# ftExtender.net
KiCad netlist of a schematic drawn in EAGLE
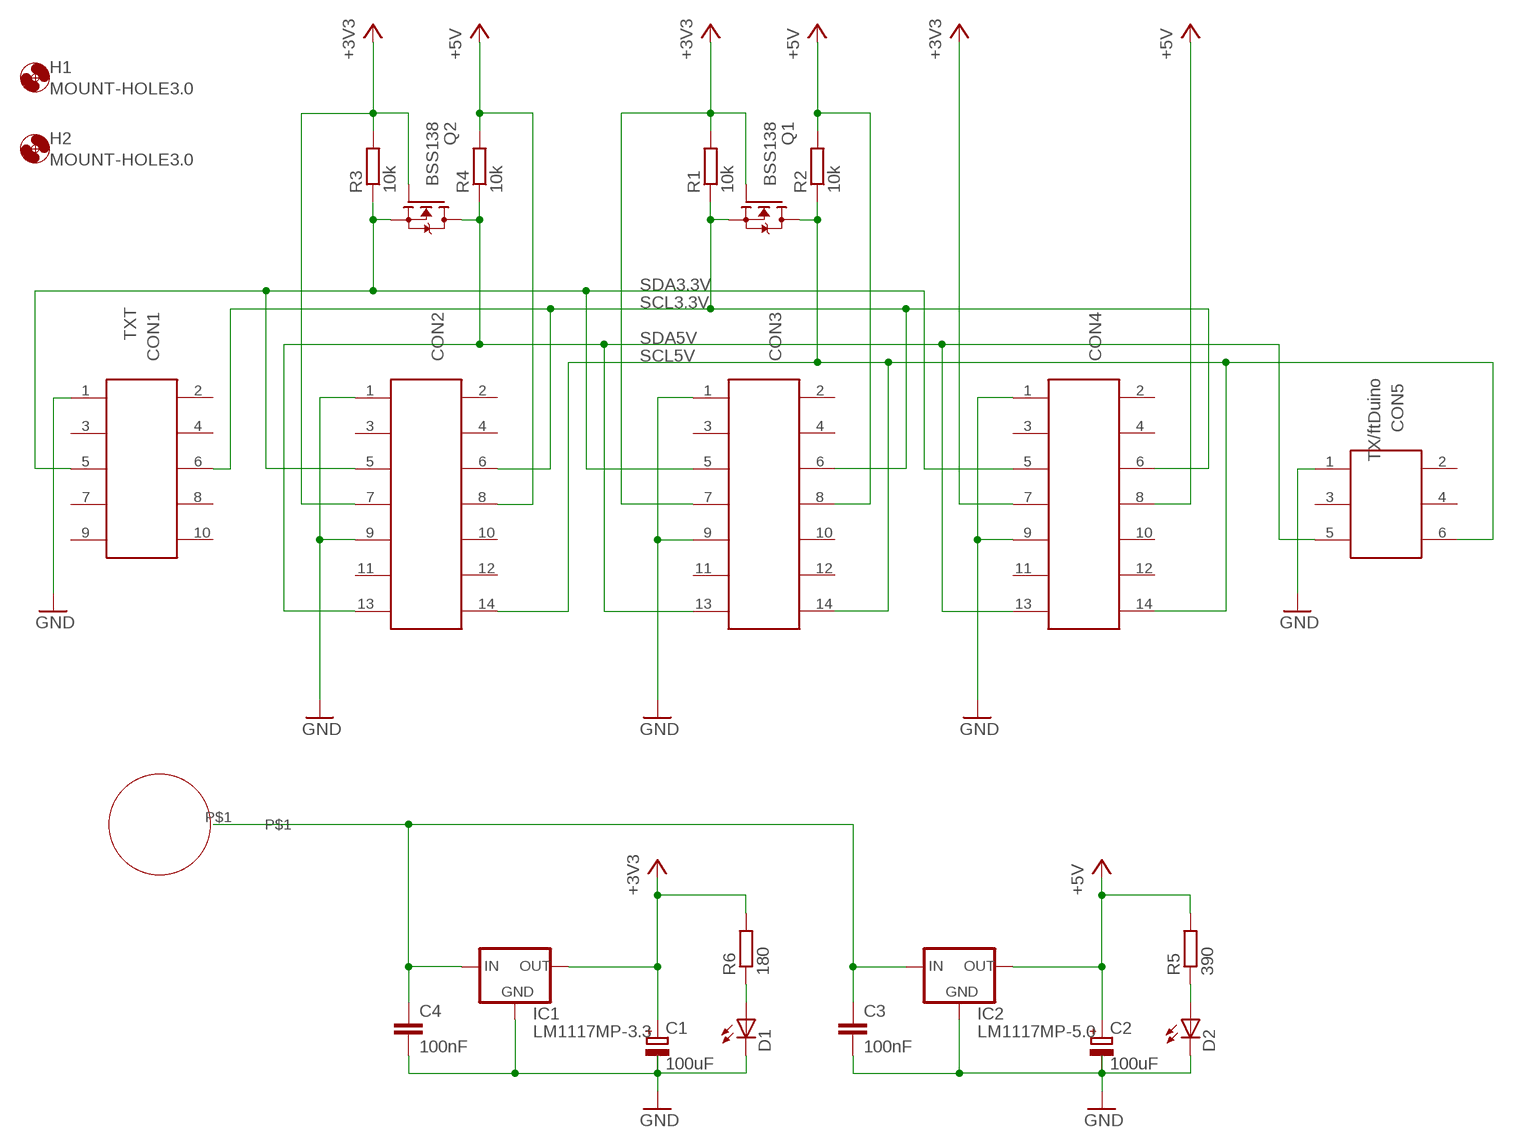
[diagram p0: schematic, sheet 1]

(export (version "E")
  (design (tool "Eeschema 10.0.6"))
  (components
    (comp (ref "+9V")
      (value "BUNDHUELSE")
      (footprint "eagle-import:BUNDHUELSE")
      (libsource (lib "eagle-import") (part "BUNDHUELSE"))
    )
    (comp (ref "C1")
      (value "100uF")
      (footprint "eagle-import:CT3528")
      (libsource (lib "eagle-import") (part "CPOL-EUCT3528"))
    )
    (comp (ref "C2")
      (value "100uF")
      (footprint "eagle-import:CT3528")
      (libsource (lib "eagle-import") (part "CPOL-EUCT3528"))
    )
    (comp (ref "C3")
      (value "100nF")
      (footprint "eagle-import:C0603K")
      (libsource (lib "eagle-import") (part "C-EUC0603K"))
    )
    (comp (ref "C4")
      (value "100nF")
      (footprint "eagle-import:C0603K")
      (libsource (lib "eagle-import") (part "C-EUC0603K"))
    )
    (comp (ref "CON1")
      (value "TXT")
      (footprint "eagle-import:612X1020621")
      (libsource (lib "eagle-import") (part "612X1020621"))
    )
    (comp (ref "CON2")
      (value "612X1420621")
      (footprint "eagle-import:612X1420621")
      (libsource (lib "eagle-import") (part "612X1420621"))
    )
    (comp (ref "CON3")
      (value "612X1420621")
      (footprint "eagle-import:612X1420621")
      (libsource (lib "eagle-import") (part "612X1420621"))
    )
    (comp (ref "CON4")
      (value "612X1420621")
      (footprint "eagle-import:612X1420621")
      (libsource (lib "eagle-import") (part "612X1420621"))
    )
    (comp (ref "CON5")
      (value "TX/ftDuino")
      (footprint "eagle-import:SMTHEADER06")
      (libsource (lib "eagle-import") (part "SMTHEADER06"))
    )
    (comp (ref "D1")
      (value "LEDCHIP-LED0805")
      (footprint "eagle-import:CHIP-LED0805")
      (libsource (lib "eagle-import") (part "LEDCHIP-LED0805"))
    )
    (comp (ref "D2")
      (value "LEDCHIP-LED0805")
      (footprint "eagle-import:CHIP-LED0805")
      (libsource (lib "eagle-import") (part "LEDCHIP-LED0805"))
    )
    (comp (ref "H1")
      (value "MOUNT-HOLE3.0")
      (footprint "eagle-import:3,0")
      (libsource (lib "eagle-import") (part "MOUNT-HOLE3.0"))
    )
    (comp (ref "H2")
      (value "MOUNT-HOLE3.0")
      (footprint "eagle-import:3,0")
      (libsource (lib "eagle-import") (part "MOUNT-HOLE3.0"))
    )
    (comp (ref "IC1")
      (value "LM1117MP-3.3")
      (footprint "eagle-import:SOT223")
      (fields (field (name "MF") "Texas Instruments"))
      (libsource (lib "eagle-import") (part "LM1117?-MP3.3"))
    )
    (comp (ref "IC2")
      (value "LM1117MP-5.0")
      (footprint "eagle-import:SOT223")
      (fields (field (name "MF") "Texas Instruments"))
      (libsource (lib "eagle-import") (part "LM1117?-MP5.0"))
    )
    (comp (ref "Q1")
      (value "BSS138")
      (footprint "eagle-import:SOT23")
      (fields (field (name "MF") "Fairchild"))
      (libsource (lib "eagle-import") (part "BSS138"))
    )
    (comp (ref "Q2")
      (value "BSS138")
      (footprint "eagle-import:SOT23")
      (fields (field (name "MF") "Fairchild"))
      (libsource (lib "eagle-import") (part "BSS138"))
    )
    (comp (ref "R1")
      (value "10k")
      (footprint "eagle-import:R0603")
      (libsource (lib "eagle-import") (part "R-EU_R0603"))
    )
    (comp (ref "R2")
      (value "10k")
      (footprint "eagle-import:R0603")
      (libsource (lib "eagle-import") (part "R-EU_R0603"))
    )
    (comp (ref "R3")
      (value "10k")
      (footprint "eagle-import:R0603")
      (libsource (lib "eagle-import") (part "R-EU_R0603"))
    )
    (comp (ref "R4")
      (value "10k")
      (footprint "eagle-import:R0603")
      (libsource (lib "eagle-import") (part "R-EU_R0603"))
    )
    (comp (ref "R5")
      (value "390")
      (footprint "eagle-import:R0603")
      (libsource (lib "eagle-import") (part "R-EU_R0603"))
    )
    (comp (ref "R6")
      (value "180")
      (footprint "eagle-import:R0603")
      (libsource (lib "eagle-import") (part "R-EU_R0603"))
    )
  )
  (nets
    (net (code "1") (name "+3V3") (class "Default")
      (node (ref "C1") (pin "-") (pinfunction "+_-") (pintype "passive"))
      (node (ref "CON2") (pin "7") (pinfunction "7_7") (pintype "passive"))
      (node (ref "CON3") (pin "7") (pinfunction "7_7") (pintype "passive"))
      (node (ref "CON4") (pin "7") (pinfunction "7_7") (pintype "passive"))
      (node (ref "IC1") (pin "2") (pinfunction "OUT_2") (pintype "passive"))
      (node (ref "IC1") (pin "4") (pinfunction "OUT_4") (pintype "passive"))
      (node (ref "Q1") (pin "1") (pinfunction "G_1") (pintype "passive"))
      (node (ref "Q2") (pin "1") (pinfunction "G_1") (pintype "passive"))
      (node (ref "R1") (pin "2") (pinfunction "2_2") (pintype "passive"))
      (node (ref "R3") (pin "2") (pinfunction "2_2") (pintype "passive"))
      (node (ref "R6") (pin "2") (pinfunction "2_2") (pintype "passive"))
    )
    (net (code "2") (name "+5V") (class "Default")
      (node (ref "C2") (pin "-") (pinfunction "+_-") (pintype "passive"))
      (node (ref "CON2") (pin "8") (pinfunction "8_8") (pintype "passive"))
      (node (ref "CON3") (pin "8") (pinfunction "8_8") (pintype "passive"))
      (node (ref "CON4") (pin "8") (pinfunction "8_8") (pintype "passive"))
      (node (ref "IC2") (pin "2") (pinfunction "OUT_2") (pintype "passive"))
      (node (ref "IC2") (pin "4") (pinfunction "OUT_4") (pintype "passive"))
      (node (ref "R2") (pin "2") (pinfunction "2_2") (pintype "passive"))
      (node (ref "R4") (pin "2") (pinfunction "2_2") (pintype "passive"))
      (node (ref "R5") (pin "2") (pinfunction "2_2") (pintype "passive"))
    )
    (net (code "3") (name "/SCL3.3V") (class "Default")
      (node (ref "CON1") (pin "6") (pinfunction "6_6") (pintype "passive"))
      (node (ref "CON2") (pin "6") (pinfunction "6_6") (pintype "passive"))
      (node (ref "CON3") (pin "6") (pinfunction "6_6") (pintype "passive"))
      (node (ref "CON4") (pin "6") (pinfunction "6_6") (pintype "passive"))
      (node (ref "Q1") (pin "2") (pinfunction "S_2") (pintype "passive"))
      (node (ref "R1") (pin "1") (pinfunction "1_1") (pintype "passive"))
    )
    (net (code "4") (name "/SCL5V") (class "Default")
      (node (ref "CON2") (pin "14") (pinfunction "14_14") (pintype "passive"))
      (node (ref "CON3") (pin "14") (pinfunction "14_14") (pintype "passive"))
      (node (ref "CON4") (pin "14") (pinfunction "14_14") (pintype "passive"))
      (node (ref "CON5") (pin "6") (pinfunction "6_6") (pintype "passive"))
      (node (ref "Q1") (pin "3") (pinfunction "D_3") (pintype "passive"))
      (node (ref "R2") (pin "1") (pinfunction "1_1") (pintype "passive"))
    )
    (net (code "5") (name "/SDA3.3V") (class "Default")
      (node (ref "CON1") (pin "5") (pinfunction "5_5") (pintype "passive"))
      (node (ref "CON2") (pin "5") (pinfunction "5_5") (pintype "passive"))
      (node (ref "CON3") (pin "5") (pinfunction "5_5") (pintype "passive"))
      (node (ref "CON4") (pin "5") (pinfunction "5_5") (pintype "passive"))
      (node (ref "Q2") (pin "2") (pinfunction "S_2") (pintype "passive"))
      (node (ref "R3") (pin "1") (pinfunction "1_1") (pintype "passive"))
    )
    (net (code "6") (name "/SDA5V") (class "Default")
      (node (ref "CON2") (pin "13") (pinfunction "13_13") (pintype "passive"))
      (node (ref "CON3") (pin "13") (pinfunction "13_13") (pintype "passive"))
      (node (ref "CON4") (pin "13") (pinfunction "13_13") (pintype "passive"))
      (node (ref "CON5") (pin "5") (pinfunction "5_5") (pintype "passive"))
      (node (ref "Q2") (pin "3") (pinfunction "D_3") (pintype "passive"))
      (node (ref "R4") (pin "1") (pinfunction "1_1") (pintype "passive"))
    )
    (net (code "7") (name "GND") (class "Default")
      (node (ref "C1") (pin "+") (pinfunction "-_+") (pintype "passive"))
      (node (ref "C2") (pin "+") (pinfunction "-_+") (pintype "passive"))
      (node (ref "C3") (pin "2") (pinfunction "2_2") (pintype "passive"))
      (node (ref "C4") (pin "2") (pinfunction "2_2") (pintype "passive"))
      (node (ref "CON1") (pin "1") (pinfunction "1_1") (pintype "passive"))
      (node (ref "CON2") (pin "1") (pinfunction "1_1") (pintype "passive"))
      (node (ref "CON2") (pin "9") (pinfunction "9_9") (pintype "passive"))
      (node (ref "CON3") (pin "1") (pinfunction "1_1") (pintype "passive"))
      (node (ref "CON3") (pin "9") (pinfunction "9_9") (pintype "passive"))
      (node (ref "CON4") (pin "1") (pinfunction "1_1") (pintype "passive"))
      (node (ref "CON4") (pin "9") (pinfunction "9_9") (pintype "passive"))
      (node (ref "CON5") (pin "1") (pinfunction "1_1") (pintype "passive"))
      (node (ref "D1") (pin "C") (pinfunction "C_C") (pintype "passive"))
      (node (ref "D2") (pin "C") (pinfunction "C_C") (pintype "passive"))
      (node (ref "IC1") (pin "1") (pinfunction "GND_1") (pintype "input"))
      (node (ref "IC2") (pin "1") (pinfunction "GND_1") (pintype "input"))
    )
    (net (code "8") (name "Net-(D1-PadA)") (class "Default")
      (node (ref "D1") (pin "A") (pinfunction "A_A") (pintype "passive"))
      (node (ref "R6") (pin "1") (pinfunction "1_1") (pintype "passive"))
    )
    (net (code "9") (name "Net-(D2-PadA)") (class "Default")
      (node (ref "D2") (pin "A") (pinfunction "A_A") (pintype "passive"))
      (node (ref "R5") (pin "1") (pinfunction "1_1") (pintype "passive"))
    )
    (net (code "10") (name "Net-(IC1-IN)") (class "Default")
      (node (ref "+9V") (pin "P$1") (pinfunction "P$1_P$1") (pintype "bidirectional"))
      (node (ref "C3") (pin "1") (pinfunction "1_1") (pintype "passive"))
      (node (ref "C4") (pin "1") (pinfunction "1_1") (pintype "passive"))
      (node (ref "IC1") (pin "3") (pinfunction "IN_3") (pintype "input"))
      (node (ref "IC2") (pin "3") (pinfunction "IN_3") (pintype "input"))
    )
    (net (code "11") (name "unconnected-(CON1-Pad2)") (class "Default")
      (node (ref "CON1") (pin "2") (pinfunction "2_2") (pintype "passive"))
    )
    (net (code "12") (name "unconnected-(CON1-Pad3)") (class "Default")
      (node (ref "CON1") (pin "3") (pinfunction "3_3") (pintype "passive"))
    )
    (net (code "13") (name "unconnected-(CON1-Pad4)") (class "Default")
      (node (ref "CON1") (pin "4") (pinfunction "4_4") (pintype "passive"))
    )
    (net (code "14") (name "unconnected-(CON1-Pad7)") (class "Default")
      (node (ref "CON1") (pin "7") (pinfunction "7_7") (pintype "passive"))
    )
    (net (code "15") (name "unconnected-(CON1-Pad8)") (class "Default")
      (node (ref "CON1") (pin "8") (pinfunction "8_8") (pintype "passive"))
    )
    (net (code "16") (name "unconnected-(CON1-Pad9)") (class "Default")
      (node (ref "CON1") (pin "9") (pinfunction "9_9") (pintype "passive"))
    )
    (net (code "17") (name "unconnected-(CON1-Pad10)") (class "Default")
      (node (ref "CON1") (pin "10") (pinfunction "10_10") (pintype "passive"))
    )
    (net (code "18") (name "unconnected-(CON2-Pad2)") (class "Default")
      (node (ref "CON2") (pin "2") (pinfunction "2_2") (pintype "passive"))
    )
    (net (code "19") (name "unconnected-(CON2-Pad3)") (class "Default")
      (node (ref "CON2") (pin "3") (pinfunction "3_3") (pintype "passive"))
    )
    (net (code "20") (name "unconnected-(CON2-Pad4)") (class "Default")
      (node (ref "CON2") (pin "4") (pinfunction "4_4") (pintype "passive"))
    )
    (net (code "21") (name "unconnected-(CON2-Pad10)") (class "Default")
      (node (ref "CON2") (pin "10") (pinfunction "10_10") (pintype "passive"))
    )
    (net (code "22") (name "unconnected-(CON2-Pad11)") (class "Default")
      (node (ref "CON2") (pin "11") (pinfunction "11_11") (pintype "passive"))
    )
    (net (code "23") (name "unconnected-(CON2-Pad12)") (class "Default")
      (node (ref "CON2") (pin "12") (pinfunction "12_12") (pintype "passive"))
    )
    (net (code "24") (name "unconnected-(CON3-Pad2)") (class "Default")
      (node (ref "CON3") (pin "2") (pinfunction "2_2") (pintype "passive"))
    )
    (net (code "25") (name "unconnected-(CON3-Pad3)") (class "Default")
      (node (ref "CON3") (pin "3") (pinfunction "3_3") (pintype "passive"))
    )
    (net (code "26") (name "unconnected-(CON3-Pad4)") (class "Default")
      (node (ref "CON3") (pin "4") (pinfunction "4_4") (pintype "passive"))
    )
    (net (code "27") (name "unconnected-(CON3-Pad10)") (class "Default")
      (node (ref "CON3") (pin "10") (pinfunction "10_10") (pintype "passive"))
    )
    (net (code "28") (name "unconnected-(CON3-Pad11)") (class "Default")
      (node (ref "CON3") (pin "11") (pinfunction "11_11") (pintype "passive"))
    )
    (net (code "29") (name "unconnected-(CON3-Pad12)") (class "Default")
      (node (ref "CON3") (pin "12") (pinfunction "12_12") (pintype "passive"))
    )
    (net (code "30") (name "unconnected-(CON4-Pad2)") (class "Default")
      (node (ref "CON4") (pin "2") (pinfunction "2_2") (pintype "passive"))
    )
    (net (code "31") (name "unconnected-(CON4-Pad3)") (class "Default")
      (node (ref "CON4") (pin "3") (pinfunction "3_3") (pintype "passive"))
    )
    (net (code "32") (name "unconnected-(CON4-Pad4)") (class "Default")
      (node (ref "CON4") (pin "4") (pinfunction "4_4") (pintype "passive"))
    )
    (net (code "33") (name "unconnected-(CON4-Pad10)") (class "Default")
      (node (ref "CON4") (pin "10") (pinfunction "10_10") (pintype "passive"))
    )
    (net (code "34") (name "unconnected-(CON4-Pad11)") (class "Default")
      (node (ref "CON4") (pin "11") (pinfunction "11_11") (pintype "passive"))
    )
    (net (code "35") (name "unconnected-(CON4-Pad12)") (class "Default")
      (node (ref "CON4") (pin "12") (pinfunction "12_12") (pintype "passive"))
    )
    (net (code "36") (name "unconnected-(CON5-Pad2)") (class "Default")
      (node (ref "CON5") (pin "2") (pinfunction "2_2") (pintype "passive"))
    )
    (net (code "37") (name "unconnected-(CON5-Pad3)") (class "Default")
      (node (ref "CON5") (pin "3") (pinfunction "3_3") (pintype "passive"))
    )
    (net (code "38") (name "unconnected-(CON5-Pad4)") (class "Default")
      (node (ref "CON5") (pin "4") (pinfunction "4_4") (pintype "passive"))
    )
  )
)
